# SparkFun_Qwiic_Mux_Shield_with_JST.net
KiCad netlist of a schematic drawn in EAGLE
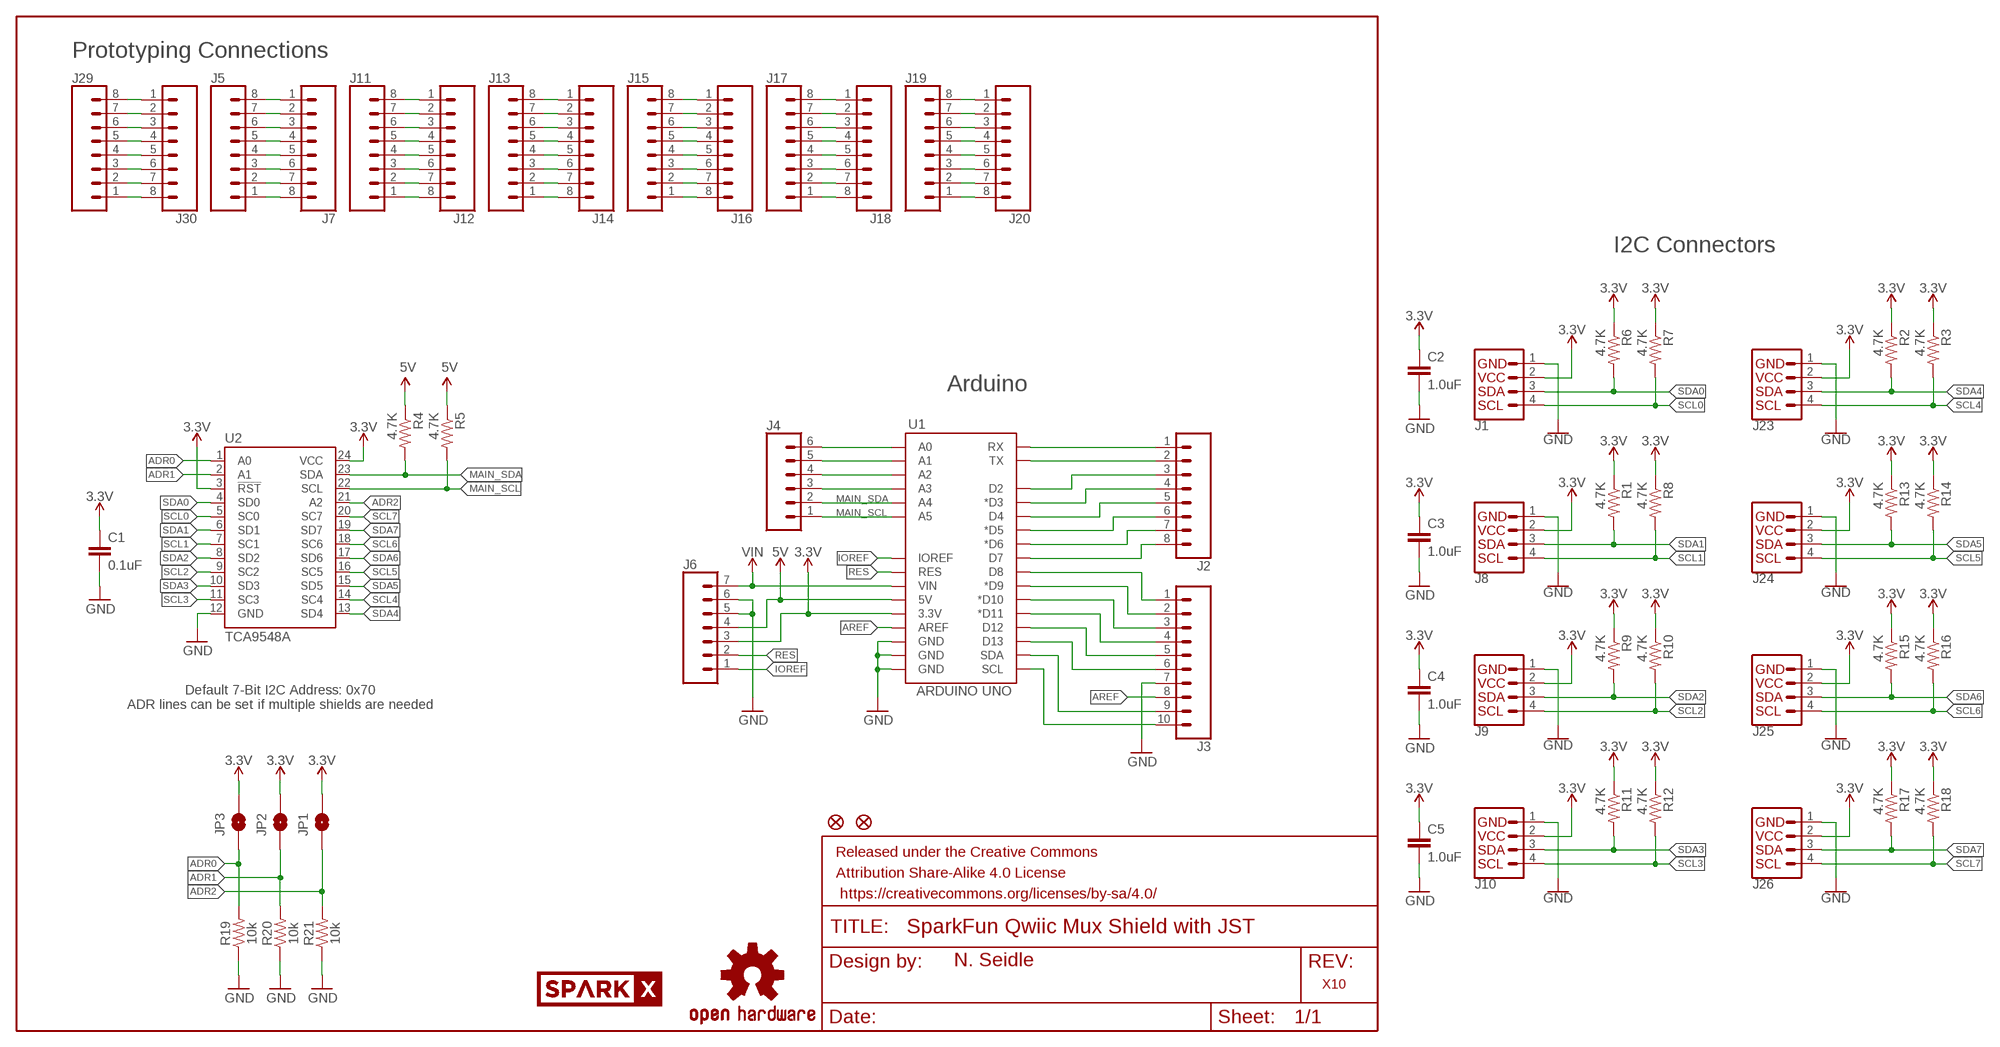
[diagram p0: schematic, sheet 1]

(export (version "E")
  (design (tool "Eeschema 10.0.6"))
  (components
    (comp (ref "C1")
      (value "0.1uF")
      (footprint "eagle-import:0603")
      (libsource (lib "eagle-import") (part "0.1UF-0603-25V-(+80/-20%)"))
    )
    (comp (ref "C2")
      (value "1.0uF")
      (footprint "eagle-import:0603")
      (libsource (lib "eagle-import") (part "1.0UF-0603-16V-10%"))
    )
    (comp (ref "C3")
      (value "1.0uF")
      (footprint "eagle-import:0603")
      (libsource (lib "eagle-import") (part "1.0UF-0603-16V-10%"))
    )
    (comp (ref "C4")
      (value "1.0uF")
      (footprint "eagle-import:0603")
      (libsource (lib "eagle-import") (part "1.0UF-0603-16V-10%"))
    )
    (comp (ref "C5")
      (value "1.0uF")
      (footprint "eagle-import:0603")
      (libsource (lib "eagle-import") (part "1.0UF-0603-16V-10%"))
    )
    (comp (ref "FD1")
      (value "FIDUCIAL1X2")
      (footprint "eagle-import:FIDUCIAL-1X2")
      (libsource (lib "eagle-import") (part "FIDUCIAL1X2"))
    )
    (comp (ref "FD2")
      (value "FIDUCIAL1X2")
      (footprint "eagle-import:FIDUCIAL-1X2")
      (libsource (lib "eagle-import") (part "FIDUCIAL1X2"))
    )
    (comp (ref "FRAME1")
      (value "FRAME-LETTER")
      (footprint "eagle-import:CREATIVE_COMMONS")
      (libsource (lib "eagle-import") (part "FRAME-LETTER"))
    )
    (comp (ref "J1")
      (value "I2C_STANDARDJS-1MM")
      (footprint "eagle-import:1X04_1MM_RA")
      (libsource (lib "eagle-import") (part "I2C_STANDARDJS-1MM"))
    )
    (comp (ref "J2")
      (value "CONN_08NO_SILK_FEMALE_PTH")
      (footprint "eagle-import:1X08_NO_SILK")
      (libsource (lib "eagle-import") (part "CONN_08NO_SILK_FEMALE_PTH"))
    )
    (comp (ref "J3")
      (value "CONN_10NO_SILK_PTH_FEMALE")
      (footprint "eagle-import:1X10_NO_SILK")
      (libsource (lib "eagle-import") (part "CONN_10NO_SILK_PTH_FEMALE"))
    )
    (comp (ref "J4")
      (value "CONN_06NO_SILK_FEMALE_PTH")
      (footprint "eagle-import:1X06_NO_SILK")
      (libsource (lib "eagle-import") (part "CONN_06NO_SILK_FEMALE_PTH"))
    )
    (comp (ref "J5")
      (value "CONN_08NO_SILK_FEMALE_PTH")
      (footprint "eagle-import:1X08_NO_SILK")
      (libsource (lib "eagle-import") (part "CONN_08NO_SILK_FEMALE_PTH"))
    )
    (comp (ref "J6")
      (value "CONN_07NO_SILK")
      (footprint "eagle-import:1X07_NO_SILK")
      (libsource (lib "eagle-import") (part "CONN_07NO_SILK"))
    )
    (comp (ref "J7")
      (value "CONN_08NO_SILK_FEMALE_PTH")
      (footprint "eagle-import:1X08_NO_SILK")
      (libsource (lib "eagle-import") (part "CONN_08NO_SILK_FEMALE_PTH"))
    )
    (comp (ref "J8")
      (value "I2C_STANDARDJS-1MM")
      (footprint "eagle-import:1X04_1MM_RA")
      (libsource (lib "eagle-import") (part "I2C_STANDARDJS-1MM"))
    )
    (comp (ref "J9")
      (value "I2C_STANDARDJS-1MM")
      (footprint "eagle-import:1X04_1MM_RA")
      (libsource (lib "eagle-import") (part "I2C_STANDARDJS-1MM"))
    )
    (comp (ref "J10")
      (value "I2C_STANDARDJS-1MM")
      (footprint "eagle-import:1X04_1MM_RA")
      (libsource (lib "eagle-import") (part "I2C_STANDARDJS-1MM"))
    )
    (comp (ref "J11")
      (value "CONN_08NO_SILK_FEMALE_PTH")
      (footprint "eagle-import:1X08_NO_SILK")
      (libsource (lib "eagle-import") (part "CONN_08NO_SILK_FEMALE_PTH"))
    )
    (comp (ref "J12")
      (value "CONN_08NO_SILK_FEMALE_PTH")
      (footprint "eagle-import:1X08_NO_SILK")
      (libsource (lib "eagle-import") (part "CONN_08NO_SILK_FEMALE_PTH"))
    )
    (comp (ref "J13")
      (value "CONN_08NO_SILK_FEMALE_PTH")
      (footprint "eagle-import:1X08_NO_SILK")
      (libsource (lib "eagle-import") (part "CONN_08NO_SILK_FEMALE_PTH"))
    )
    (comp (ref "J14")
      (value "CONN_08NO_SILK_FEMALE_PTH")
      (footprint "eagle-import:1X08_NO_SILK")
      (libsource (lib "eagle-import") (part "CONN_08NO_SILK_FEMALE_PTH"))
    )
    (comp (ref "J15")
      (value "CONN_08NO_SILK_FEMALE_PTH")
      (footprint "eagle-import:1X08_NO_SILK")
      (libsource (lib "eagle-import") (part "CONN_08NO_SILK_FEMALE_PTH"))
    )
    (comp (ref "J16")
      (value "CONN_08NO_SILK_FEMALE_PTH")
      (footprint "eagle-import:1X08_NO_SILK")
      (libsource (lib "eagle-import") (part "CONN_08NO_SILK_FEMALE_PTH"))
    )
    (comp (ref "J17")
      (value "CONN_08NO_SILK_FEMALE_PTH")
      (footprint "eagle-import:1X08_NO_SILK")
      (libsource (lib "eagle-import") (part "CONN_08NO_SILK_FEMALE_PTH"))
    )
    (comp (ref "J18")
      (value "CONN_08NO_SILK_FEMALE_PTH")
      (footprint "eagle-import:1X08_NO_SILK")
      (libsource (lib "eagle-import") (part "CONN_08NO_SILK_FEMALE_PTH"))
    )
    (comp (ref "J19")
      (value "CONN_08NO_SILK_FEMALE_PTH")
      (footprint "eagle-import:1X08_NO_SILK")
      (libsource (lib "eagle-import") (part "CONN_08NO_SILK_FEMALE_PTH"))
    )
    (comp (ref "J20")
      (value "CONN_08NO_SILK_FEMALE_PTH")
      (footprint "eagle-import:1X08_NO_SILK")
      (libsource (lib "eagle-import") (part "CONN_08NO_SILK_FEMALE_PTH"))
    )
    (comp (ref "J23")
      (value "I2C_STANDARDSILK")
      (footprint "eagle-import:1X04")
      (libsource (lib "eagle-import") (part "I2C_STANDARDSILK"))
    )
    (comp (ref "J24")
      (value "I2C_STANDARDSILK")
      (footprint "eagle-import:1X04")
      (libsource (lib "eagle-import") (part "I2C_STANDARDSILK"))
    )
    (comp (ref "J25")
      (value "I2C_STANDARDSILK")
      (footprint "eagle-import:1X04")
      (libsource (lib "eagle-import") (part "I2C_STANDARDSILK"))
    )
    (comp (ref "J26")
      (value "I2C_STANDARDSILK")
      (footprint "eagle-import:1X04")
      (libsource (lib "eagle-import") (part "I2C_STANDARDSILK"))
    )
    (comp (ref "J29")
      (value "CONN_08NO_SILK_FEMALE_PTH")
      (footprint "eagle-import:1X08_NO_SILK")
      (libsource (lib "eagle-import") (part "CONN_08NO_SILK_FEMALE_PTH"))
    )
    (comp (ref "J30")
      (value "CONN_08NO_SILK_FEMALE_PTH")
      (footprint "eagle-import:1X08_NO_SILK")
      (libsource (lib "eagle-import") (part "CONN_08NO_SILK_FEMALE_PTH"))
    )
    (comp (ref "JP1")
      (value "JUMPER-SMT_2_NO_SILK")
      (footprint "eagle-import:SMT-JUMPER_2_NO_SILK")
      (libsource (lib "eagle-import") (part "JUMPER-SMT_2_NO_SILK"))
    )
    (comp (ref "JP2")
      (value "JUMPER-SMT_2_NO_SILK")
      (footprint "eagle-import:SMT-JUMPER_2_NO_SILK")
      (libsource (lib "eagle-import") (part "JUMPER-SMT_2_NO_SILK"))
    )
    (comp (ref "JP3")
      (value "JUMPER-SMT_2_NO_SILK")
      (footprint "eagle-import:SMT-JUMPER_2_NO_SILK")
      (libsource (lib "eagle-import") (part "JUMPER-SMT_2_NO_SILK"))
    )
    (comp (ref "LOGO1")
      (value "OSHW-LOGOMINI")
      (footprint "eagle-import:OSHW-LOGO-MINI")
      (libsource (lib "eagle-import") (part "OSHW-LOGOMINI"))
    )
    (comp (ref "R1")
      (value "4.7K")
      (footprint "eagle-import:0603-RES")
      (libsource (lib "eagle-import") (part "4.7KOHM-1/10W-1%(0603)"))
    )
    (comp (ref "R2")
      (value "4.7K")
      (footprint "eagle-import:0603-RES")
      (libsource (lib "eagle-import") (part "4.7KOHM-1/10W-1%(0603)"))
    )
    (comp (ref "R3")
      (value "4.7K")
      (footprint "eagle-import:0603-RES")
      (libsource (lib "eagle-import") (part "4.7KOHM-1/10W-1%(0603)"))
    )
    (comp (ref "R4")
      (value "4.7K")
      (footprint "eagle-import:0603-RES")
      (libsource (lib "eagle-import") (part "4.7KOHM-1/10W-1%(0603)"))
    )
    (comp (ref "R5")
      (value "4.7K")
      (footprint "eagle-import:0603-RES")
      (libsource (lib "eagle-import") (part "4.7KOHM-1/10W-1%(0603)"))
    )
    (comp (ref "R6")
      (value "4.7K")
      (footprint "eagle-import:0603-RES")
      (libsource (lib "eagle-import") (part "4.7KOHM-1/10W-1%(0603)"))
    )
    (comp (ref "R7")
      (value "4.7K")
      (footprint "eagle-import:0603-RES")
      (libsource (lib "eagle-import") (part "4.7KOHM-1/10W-1%(0603)"))
    )
    (comp (ref "R8")
      (value "4.7K")
      (footprint "eagle-import:0603-RES")
      (libsource (lib "eagle-import") (part "4.7KOHM-1/10W-1%(0603)"))
    )
    (comp (ref "R9")
      (value "4.7K")
      (footprint "eagle-import:0603-RES")
      (libsource (lib "eagle-import") (part "4.7KOHM-1/10W-1%(0603)"))
    )
    (comp (ref "R10")
      (value "4.7K")
      (footprint "eagle-import:0603-RES")
      (libsource (lib "eagle-import") (part "4.7KOHM-1/10W-1%(0603)"))
    )
    (comp (ref "R11")
      (value "4.7K")
      (footprint "eagle-import:0603-RES")
      (libsource (lib "eagle-import") (part "4.7KOHM-1/10W-1%(0603)"))
    )
    (comp (ref "R12")
      (value "4.7K")
      (footprint "eagle-import:0603-RES")
      (libsource (lib "eagle-import") (part "4.7KOHM-1/10W-1%(0603)"))
    )
    (comp (ref "R13")
      (value "4.7K")
      (footprint "eagle-import:0603-RES")
      (libsource (lib "eagle-import") (part "4.7KOHM-1/10W-1%(0603)"))
    )
    (comp (ref "R14")
      (value "4.7K")
      (footprint "eagle-import:0603-RES")
      (libsource (lib "eagle-import") (part "4.7KOHM-1/10W-1%(0603)"))
    )
    (comp (ref "R15")
      (value "4.7K")
      (footprint "eagle-import:0603-RES")
      (libsource (lib "eagle-import") (part "4.7KOHM-1/10W-1%(0603)"))
    )
    (comp (ref "R16")
      (value "4.7K")
      (footprint "eagle-import:0603-RES")
      (libsource (lib "eagle-import") (part "4.7KOHM-1/10W-1%(0603)"))
    )
    (comp (ref "R17")
      (value "4.7K")
      (footprint "eagle-import:0603-RES")
      (libsource (lib "eagle-import") (part "4.7KOHM-1/10W-1%(0603)"))
    )
    (comp (ref "R18")
      (value "4.7K")
      (footprint "eagle-import:0603-RES")
      (libsource (lib "eagle-import") (part "4.7KOHM-1/10W-1%(0603)"))
    )
    (comp (ref "R19")
      (value "10k")
      (footprint "eagle-import:0603")
      (libsource (lib "eagle-import") (part "10KOHM-0603-1/10W-1%"))
    )
    (comp (ref "R20")
      (value "10k")
      (footprint "eagle-import:0603")
      (libsource (lib "eagle-import") (part "10KOHM-0603-1/10W-1%"))
    )
    (comp (ref "R21")
      (value "10k")
      (footprint "eagle-import:0603")
      (libsource (lib "eagle-import") (part "10KOHM-0603-1/10W-1%"))
    )
    (comp (ref "U$1")
      (value "SPARKX-LOGO3")
      (footprint "eagle-import:SPARKX-SMALL")
      (libsource (lib "eagle-import") (part "SPARKX-LOGO3"))
    )
    (comp (ref "U$2")
      (value "SPARKX-LOGO5")
      (footprint "eagle-import:SPARKX-LARGE")
      (libsource (lib "eagle-import") (part "SPARKX-LOGO5"))
    )
    (comp (ref "U1")
      (value "ARDUINO UNO")
      (footprint "eagle-import:UNO_R3_SHIELD_NOLABELS")
      (libsource (lib "eagle-import") (part "ARDUINO_R3_SHIELDNOLABELS"))
    )
    (comp (ref "U2")
      (value "TCA9548A")
      (footprint "eagle-import:TSSOP28")
      (libsource (lib "eagle-import") (part "TCA9548A"))
    )
  )
  (nets
    (net (code "1") (name "3.3V") (class "Default")
      (node (ref "C1") (pin "1") (pinfunction "1_1") (pintype "passive"))
      (node (ref "C2") (pin "1") (pinfunction "1_1") (pintype "passive"))
      (node (ref "C3") (pin "1") (pinfunction "1_1") (pintype "passive"))
      (node (ref "C4") (pin "1") (pinfunction "1_1") (pintype "passive"))
      (node (ref "C5") (pin "1") (pinfunction "1_1") (pintype "passive"))
      (node (ref "J1") (pin "2") (pinfunction "VCC_2") (pintype "power_in"))
      (node (ref "J10") (pin "2") (pinfunction "VCC_2") (pintype "power_in"))
      (node (ref "J23") (pin "2") (pinfunction "VCC_2") (pintype "power_in"))
      (node (ref "J24") (pin "2") (pinfunction "VCC_2") (pintype "power_in"))
      (node (ref "J25") (pin "2") (pinfunction "VCC_2") (pintype "power_in"))
      (node (ref "J26") (pin "2") (pinfunction "VCC_2") (pintype "power_in"))
      (node (ref "J6") (pin "3") (pinfunction "3_3") (pintype "passive"))
      (node (ref "J8") (pin "2") (pinfunction "VCC_2") (pintype "power_in"))
      (node (ref "J9") (pin "2") (pinfunction "VCC_2") (pintype "power_in"))
      (node (ref "JP1") (pin "2") (pinfunction "2_2") (pintype "passive"))
      (node (ref "JP2") (pin "2") (pinfunction "2_2") (pintype "passive"))
      (node (ref "JP3") (pin "2") (pinfunction "2_2") (pintype "passive"))
      (node (ref "R1") (pin "1") (pinfunction "1_1") (pintype "passive"))
      (node (ref "R10") (pin "1") (pinfunction "1_1") (pintype "passive"))
      (node (ref "R11") (pin "1") (pinfunction "1_1") (pintype "passive"))
      (node (ref "R12") (pin "1") (pinfunction "1_1") (pintype "passive"))
      (node (ref "R13") (pin "1") (pinfunction "1_1") (pintype "passive"))
      (node (ref "R14") (pin "1") (pinfunction "1_1") (pintype "passive"))
      (node (ref "R15") (pin "1") (pinfunction "1_1") (pintype "passive"))
      (node (ref "R16") (pin "1") (pinfunction "1_1") (pintype "passive"))
      (node (ref "R17") (pin "1") (pinfunction "1_1") (pintype "passive"))
      (node (ref "R18") (pin "1") (pinfunction "1_1") (pintype "passive"))
      (node (ref "R2") (pin "1") (pinfunction "1_1") (pintype "passive"))
      (node (ref "R3") (pin "1") (pinfunction "1_1") (pintype "passive"))
      (node (ref "R6") (pin "1") (pinfunction "1_1") (pintype "passive"))
      (node (ref "R7") (pin "1") (pinfunction "1_1") (pintype "passive"))
      (node (ref "R8") (pin "1") (pinfunction "1_1") (pintype "passive"))
      (node (ref "R9") (pin "1") (pinfunction "1_1") (pintype "passive"))
      (node (ref "U1") (pin "3.3V") (pinfunction "3.3V_3.3V") (pintype "bidirectional"))
      (node (ref "U2") (pin "24") (pinfunction "VCC_24") (pintype "bidirectional"))
      (node (ref "U2") (pin "3") (pinfunction "~{RST}_3") (pintype "bidirectional"))
    )
    (net (code "2") (name "5V") (class "Default")
      (node (ref "J6") (pin "4") (pinfunction "4_4") (pintype "passive"))
      (node (ref "R4") (pin "1") (pinfunction "1_1") (pintype "passive"))
      (node (ref "R5") (pin "1") (pinfunction "1_1") (pintype "passive"))
      (node (ref "U1") (pin "5V") (pinfunction "5V_5V") (pintype "bidirectional"))
    )
    (net (code "3") (name "ADR0") (class "Default")
      (node (ref "JP3") (pin "1") (pinfunction "1_1") (pintype "passive"))
      (node (ref "R19") (pin "2") (pinfunction "2_2") (pintype "passive"))
      (node (ref "U2") (pin "1") (pinfunction "A0_1") (pintype "bidirectional"))
    )
    (net (code "4") (name "ADR1") (class "Default")
      (node (ref "JP2") (pin "1") (pinfunction "1_1") (pintype "passive"))
      (node (ref "R20") (pin "2") (pinfunction "2_2") (pintype "passive"))
      (node (ref "U2") (pin "2") (pinfunction "A1_2") (pintype "bidirectional"))
    )
    (net (code "5") (name "ADR2") (class "Default")
      (node (ref "JP1") (pin "1") (pinfunction "1_1") (pintype "passive"))
      (node (ref "R21") (pin "2") (pinfunction "2_2") (pintype "passive"))
      (node (ref "U2") (pin "21") (pinfunction "A2_21") (pintype "bidirectional"))
    )
    (net (code "6") (name "AREF") (class "Default")
      (node (ref "J3") (pin "8") (pinfunction "8_8") (pintype "passive"))
      (node (ref "U1") (pin "AREF") (pinfunction "AREF_AREF") (pintype "bidirectional"))
    )
    (net (code "7") (name "GND") (class "Default")
      (node (ref "C1") (pin "2") (pinfunction "2_2") (pintype "passive"))
      (node (ref "C2") (pin "2") (pinfunction "2_2") (pintype "passive"))
      (node (ref "C3") (pin "2") (pinfunction "2_2") (pintype "passive"))
      (node (ref "C4") (pin "2") (pinfunction "2_2") (pintype "passive"))
      (node (ref "C5") (pin "2") (pinfunction "2_2") (pintype "passive"))
      (node (ref "J1") (pin "1") (pinfunction "GND_1") (pintype "power_in"))
      (node (ref "J10") (pin "1") (pinfunction "GND_1") (pintype "power_in"))
      (node (ref "J23") (pin "1") (pinfunction "GND_1") (pintype "power_in"))
      (node (ref "J24") (pin "1") (pinfunction "GND_1") (pintype "power_in"))
      (node (ref "J25") (pin "1") (pinfunction "GND_1") (pintype "power_in"))
      (node (ref "J26") (pin "1") (pinfunction "GND_1") (pintype "power_in"))
      (node (ref "J3") (pin "7") (pinfunction "7_7") (pintype "passive"))
      (node (ref "J6") (pin "5") (pinfunction "5_5") (pintype "passive"))
      (node (ref "J6") (pin "6") (pinfunction "6_6") (pintype "passive"))
      (node (ref "J8") (pin "1") (pinfunction "GND_1") (pintype "power_in"))
      (node (ref "J9") (pin "1") (pinfunction "GND_1") (pintype "power_in"))
      (node (ref "R19") (pin "1") (pinfunction "1_1") (pintype "passive"))
      (node (ref "R20") (pin "1") (pinfunction "1_1") (pintype "passive"))
      (node (ref "R21") (pin "1") (pinfunction "1_1") (pintype "passive"))
      (node (ref "U1") (pin "GND@0") (pinfunction "GND_GND@0") (pintype "bidirectional"))
      (node (ref "U1") (pin "GND@1") (pinfunction "GND_GND@1") (pintype "bidirectional"))
      (node (ref "U1") (pin "GND@2") (pinfunction "GND_GND@2") (pintype "bidirectional"))
      (node (ref "U2") (pin "12") (pinfunction "GND_12") (pintype "bidirectional"))
    )
    (net (code "8") (name "IOREF") (class "Default")
      (node (ref "J6") (pin "1") (pinfunction "1_1") (pintype "passive"))
      (node (ref "U1") (pin "IOREF") (pinfunction "IOREF_IOREF") (pintype "bidirectional"))
    )
    (net (code "9") (name "MAIN_SCL") (class "Default")
      (node (ref "J4") (pin "1") (pinfunction "1_1") (pintype "passive"))
      (node (ref "R5") (pin "2") (pinfunction "2_2") (pintype "passive"))
      (node (ref "U1") (pin "A5") (pinfunction "A5_A5") (pintype "bidirectional"))
      (node (ref "U2") (pin "22") (pinfunction "SCL_22") (pintype "bidirectional"))
    )
    (net (code "10") (name "MAIN_SDA") (class "Default")
      (node (ref "J4") (pin "2") (pinfunction "2_2") (pintype "passive"))
      (node (ref "R4") (pin "2") (pinfunction "2_2") (pintype "passive"))
      (node (ref "U1") (pin "A4") (pinfunction "A4_A4") (pintype "bidirectional"))
      (node (ref "U2") (pin "23") (pinfunction "SDA_23") (pintype "bidirectional"))
    )
    (net (code "11") (name "Net-(J2-Pad1)") (class "Default")
      (node (ref "J2") (pin "1") (pinfunction "1_1") (pintype "passive"))
      (node (ref "U1") (pin "RX") (pinfunction "RX_RX") (pintype "bidirectional"))
    )
    (net (code "12") (name "Net-(J2-Pad2)") (class "Default")
      (node (ref "J2") (pin "2") (pinfunction "2_2") (pintype "passive"))
      (node (ref "U1") (pin "TX") (pinfunction "TX_TX") (pintype "bidirectional"))
    )
    (net (code "13") (name "Net-(J2-Pad3)") (class "Default")
      (node (ref "J2") (pin "3") (pinfunction "3_3") (pintype "passive"))
      (node (ref "U1") (pin "D2") (pinfunction "D2_D2") (pintype "bidirectional"))
    )
    (net (code "14") (name "Net-(J2-Pad5)") (class "Default")
      (node (ref "J2") (pin "5") (pinfunction "5_5") (pintype "passive"))
      (node (ref "U1") (pin "D4") (pinfunction "D4_D4") (pintype "bidirectional"))
    )
    (net (code "15") (name "Net-(J2-Pad8)") (class "Default")
      (node (ref "J2") (pin "8") (pinfunction "8_8") (pintype "passive"))
      (node (ref "U1") (pin "D7") (pinfunction "D7_D7") (pintype "bidirectional"))
    )
    (net (code "16") (name "Net-(J3-Pad1)") (class "Default")
      (node (ref "J3") (pin "1") (pinfunction "1_1") (pintype "passive"))
      (node (ref "U1") (pin "D8") (pinfunction "D8_D8") (pintype "bidirectional"))
    )
    (net (code "17") (name "Net-(J3-Pad5)") (class "Default")
      (node (ref "J3") (pin "5") (pinfunction "5_5") (pintype "passive"))
      (node (ref "U1") (pin "D12") (pinfunction "D12_D12") (pintype "bidirectional"))
    )
    (net (code "18") (name "Net-(J3-Pad6)") (class "Default")
      (node (ref "J3") (pin "6") (pinfunction "6_6") (pintype "passive"))
      (node (ref "U1") (pin "D13") (pinfunction "D13_D13") (pintype "bidirectional"))
    )
    (net (code "19") (name "Net-(J3-Pad9)") (class "Default")
      (node (ref "J3") (pin "9") (pinfunction "9_9") (pintype "passive"))
      (node (ref "U1") (pin "SDA") (pinfunction "SDA_SDA") (pintype "bidirectional"))
    )
    (net (code "20") (name "Net-(J3-Pad10)") (class "Default")
      (node (ref "J3") (pin "10") (pinfunction "10_10") (pintype "passive"))
      (node (ref "U1") (pin "SCL") (pinfunction "SCL_SCL") (pintype "bidirectional"))
    )
    (net (code "21") (name "Net-(J4-Pad3)") (class "Default")
      (node (ref "J4") (pin "3") (pinfunction "3_3") (pintype "passive"))
      (node (ref "U1") (pin "A3") (pinfunction "A3_A3") (pintype "bidirectional"))
    )
    (net (code "22") (name "Net-(J4-Pad4)") (class "Default")
      (node (ref "J4") (pin "4") (pinfunction "4_4") (pintype "passive"))
      (node (ref "U1") (pin "A2") (pinfunction "A2_A2") (pintype "bidirectional"))
    )
    (net (code "23") (name "Net-(J4-Pad5)") (class "Default")
      (node (ref "J4") (pin "5") (pinfunction "5_5") (pintype "passive"))
      (node (ref "U1") (pin "A1") (pinfunction "A1_A1") (pintype "bidirectional"))
    )
    (net (code "24") (name "Net-(J4-Pad6)") (class "Default")
      (node (ref "J4") (pin "6") (pinfunction "6_6") (pintype "passive"))
      (node (ref "U1") (pin "A0") (pinfunction "A0_A0") (pintype "bidirectional"))
    )
    (net (code "25") (name "Net-(J5-Pad1)") (class "Default")
      (node (ref "J5") (pin "1") (pinfunction "1_1") (pintype "passive"))
      (node (ref "J7") (pin "8") (pinfunction "8_8") (pintype "passive"))
    )
    (net (code "26") (name "Net-(J5-Pad2)") (class "Default")
      (node (ref "J5") (pin "2") (pinfunction "2_2") (pintype "passive"))
      (node (ref "J7") (pin "7") (pinfunction "7_7") (pintype "passive"))
    )
    (net (code "27") (name "Net-(J5-Pad3)") (class "Default")
      (node (ref "J5") (pin "3") (pinfunction "3_3") (pintype "passive"))
      (node (ref "J7") (pin "6") (pinfunction "6_6") (pintype "passive"))
    )
    (net (code "28") (name "Net-(J5-Pad4)") (class "Default")
      (node (ref "J5") (pin "4") (pinfunction "4_4") (pintype "passive"))
      (node (ref "J7") (pin "5") (pinfunction "5_5") (pintype "passive"))
    )
    (net (code "29") (name "Net-(J5-Pad5)") (class "Default")
      (node (ref "J5") (pin "5") (pinfunction "5_5") (pintype "passive"))
      (node (ref "J7") (pin "4") (pinfunction "4_4") (pintype "passive"))
    )
    (net (code "30") (name "Net-(J5-Pad6)") (class "Default")
      (node (ref "J5") (pin "6") (pinfunction "6_6") (pintype "passive"))
      (node (ref "J7") (pin "3") (pinfunction "3_3") (pintype "passive"))
    )
    (net (code "31") (name "Net-(J5-Pad7)") (class "Default")
      (node (ref "J5") (pin "7") (pinfunction "7_7") (pintype "passive"))
      (node (ref "J7") (pin "2") (pinfunction "2_2") (pintype "passive"))
    )
    (net (code "32") (name "Net-(J5-Pad8)") (class "Default")
      (node (ref "J5") (pin "8") (pinfunction "8_8") (pintype "passive"))
      (node (ref "J7") (pin "1") (pinfunction "1_1") (pintype "passive"))
    )
    (net (code "33") (name "Net-(J11-Pad1)") (class "Default")
      (node (ref "J11") (pin "1") (pinfunction "1_1") (pintype "passive"))
      (node (ref "J12") (pin "8") (pinfunction "8_8") (pintype "passive"))
    )
    (net (code "34") (name "Net-(J11-Pad2)") (class "Default")
      (node (ref "J11") (pin "2") (pinfunction "2_2") (pintype "passive"))
      (node (ref "J12") (pin "7") (pinfunction "7_7") (pintype "passive"))
    )
    (net (code "35") (name "Net-(J11-Pad3)") (class "Default")
      (node (ref "J11") (pin "3") (pinfunction "3_3") (pintype "passive"))
      (node (ref "J12") (pin "6") (pinfunction "6_6") (pintype "passive"))
    )
    (net (code "36") (name "Net-(J11-Pad4)") (class "Default")
      (node (ref "J11") (pin "4") (pinfunction "4_4") (pintype "passive"))
      (node (ref "J12") (pin "5") (pinfunction "5_5") (pintype "passive"))
    )
    (net (code "37") (name "Net-(J11-Pad5)") (class "Default")
      (node (ref "J11") (pin "5") (pinfunction "5_5") (pintype "passive"))
      (node (ref "J12") (pin "4") (pinfunction "4_4") (pintype "passive"))
    )
    (net (code "38") (name "Net-(J11-Pad6)") (class "Default")
      (node (ref "J11") (pin "6") (pinfunction "6_6") (pintype "passive"))
      (node (ref "J12") (pin "3") (pinfunction "3_3") (pintype "passive"))
    )
    (net (code "39") (name "Net-(J11-Pad7)") (class "Default")
      (node (ref "J11") (pin "7") (pinfunction "7_7") (pintype "passive"))
      (node (ref "J12") (pin "2") (pinfunction "2_2") (pintype "passive"))
    )
    (net (code "40") (name "Net-(J11-Pad8)") (class "Default")
      (node (ref "J11") (pin "8") (pinfunction "8_8") (pintype "passive"))
      (node (ref "J12") (pin "1") (pinfunction "1_1") (pintype "passive"))
    )
    (net (code "41") (name "Net-(J13-Pad1)") (class "Default")
      (node (ref "J13") (pin "1") (pinfunction "1_1") (pintype "passive"))
      (node (ref "J14") (pin "8") (pinfunction "8_8") (pintype "passive"))
    )
    (net (code "42") (name "Net-(J13-Pad2)") (class "Default")
      (node (ref "J13") (pin "2") (pinfunction "2_2") (pintype "passive"))
      (node (ref "J14") (pin "7") (pinfunction "7_7") (pintype "passive"))
    )
    (net (code "43") (name "Net-(J13-Pad3)") (class "Default")
      (node (ref "J13") (pin "3") (pinfunction "3_3") (pintype "passive"))
      (node (ref "J14") (pin "6") (pinfunction "6_6") (pintype "passive"))
    )
    (net (code "44") (name "Net-(J13-Pad4)") (class "Default")
      (node (ref "J13") (pin "4") (pinfunction "4_4") (pintype "passive"))
      (node (ref "J14") (pin "5") (pinfunction "5_5") (pintype "passive"))
    )
    (net (code "45") (name "Net-(J13-Pad5)") (class "Default")
      (node (ref "J13") (pin "5") (pinfunction "5_5") (pintype "passive"))
      (node (ref "J14") (pin "4") (pinfunction "4_4") (pintype "passive"))
    )
    (net (code "46") (name "Net-(J13-Pad6)") (class "Default")
      (node (ref "J13") (pin "6") (pinfunction "6_6") (pintype "passive"))
      (node (ref "J14") (pin "3") (pinfunction "3_3") (pintype "passive"))
    )
    (net (code "47") (name "Net-(J13-Pad7)") (class "Default")
      (node (ref "J13") (pin "7") (pinfunction "7_7") (pintype "passive"))
      (node (ref "J14") (pin "2") (pinfunction "2_2") (pintype "passive"))
    )
    (net (code "48") (name "Net-(J13-Pad8)") (class "Default")
      (node (ref "J13") (pin "8") (pinfunction "8_8") (pintype "passive"))
      (node (ref "J14") (pin "1") (pinfunction "1_1") (pintype "passive"))
    )
    (net (code "49") (name "Net-(J15-Pad1)") (class "Default")
      (node (ref "J15") (pin "1") (pinfunction "1_1") (pintype "passive"))
      (node (ref "J16") (pin "8") (pinfunction "8_8") (pintype "passive"))
    )
    (net (code "50") (name "Net-(J15-Pad2)") (class "Default")
      (node (ref "J15") (pin "2") (pinfunction "2_2") (pintype "passive"))
      (node (ref "J16") (pin "7") (pinfunction "7_7") (pintype "passive"))
    )
    (net (code "51") (name "Net-(J15-Pad3)") (class "Default")
      (node (ref "J15") (pin "3") (pinfunction "3_3") (pintype "passive"))
      (node (ref "J16") (pin "6") (pinfunction "6_6") (pintype "passive"))
    )
    (net (code "52") (name "Net-(J15-Pad4)") (class "Default")
      (node (ref "J15") (pin "4") (pinfunction "4_4") (pintype "passive"))
      (node (ref "J16") (pin "5") (pinfunction "5_5") (pintype "passive"))
    )
    (net (code "53") (name "Net-(J15-Pad5)") (class "Default")
      (node (ref "J15") (pin "5") (pinfunction "5_5") (pintype "passive"))
      (node (ref "J16") (pin "4") (pinfunction "4_4") (pintype "passive"))
    )
    (net (code "54") (name "Net-(J15-Pad6)") (class "Default")
      (node (ref "J15") (pin "6") (pinfunction "6_6") (pintype "passive"))
      (node (ref "J16") (pin "3") (pinfunction "3_3") (pintype "passive"))
    )
    (net (code "55") (name "Net-(J15-Pad7)") (class "Default")
      (node (ref "J15") (pin "7") (pinfunction "7_7") (pintype "passive"))
      (node (ref "J16") (pin "2") (pinfunction "2_2") (pintype "passive"))
    )
    (net (code "56") (name "Net-(J15-Pad8)") (class "Default")
      (node (ref "J15") (pin "8") (pinfunction "8_8") (pintype "passive"))
      (node (ref "J16") (pin "1") (pinfunction "1_1") (pintype "passive"))
    )
    (net (code "57") (name "Net-(J17-Pad1)") (class "Default")
      (node (ref "J17") (pin "1") (pinfunction "1_1") (pintype "passive"))
      (node (ref "J18") (pin "8") (pinfunction "8_8") (pintype "passive"))
    )
    (net (code "58") (name "Net-(J17-Pad2)") (class "Default")
      (node (ref "J17") (pin "2") (pinfunction "2_2") (pintype "passive"))
      (node (ref "J18") (pin "7") (pinfunction "7_7") (pintype "passive"))
    )
    (net (code "59") (name "Net-(J17-Pad3)") (class "Default")
      (node (ref "J17") (pin "3") (pinfunction "3_3") (pintype "passive"))
      (node (ref "J18") (pin "6") (pinfunction "6_6") (pintype "passive"))
    )
    (net (code "60") (name "Net-(J17-Pad4)") (class "Default")
      (node (ref "J17") (pin "4") (pinfunction "4_4") (pintype "passive"))
      (node (ref "J18") (pin "5") (pinfunction "5_5") (pintype "passive"))
    )
    (net (code "61") (name "Net-(J17-Pad5)") (class "Default")
      (node (ref "J17") (pin "5") (pinfunction "5_5") (pintype "passive"))
      (node (ref "J18") (pin "4") (pinfunction "4_4") (pintype "passive"))
    )
    (net (code "62") (name "Net-(J17-Pad6)") (class "Default")
      (node (ref "J17") (pin "6") (pinfunction "6_6") (pintype "passive"))
      (node (ref "J18") (pin "3") (pinfunction "3_3") (pintype "passive"))
    )
    (net (code "63") (name "Net-(J17-Pad7)") (class "Default")
      (node (ref "J17") (pin "7") (pinfunction "7_7") (pintype "passive"))
      (node (ref "J18") (pin "2") (pinfunction "2_2") (pintype "passive"))
    )
    (net (code "64") (name "Net-(J17-Pad8)") (class "Default")
      (node (ref "J17") (pin "8") (pinfunction "8_8") (pintype "passive"))
      (node (ref "J18") (pin "1") (pinfunction "1_1") (pintype "passive"))
    )
    (net (code "65") (name "Net-(J19-Pad1)") (class "Default")
      (node (ref "J19") (pin "1") (pinfunction "1_1") (pintype "passive"))
      (node (ref "J20") (pin "8") (pinfunction "8_8") (pintype "passive"))
    )
    (net (code "66") (name "Net-(J19-Pad2)") (class "Default")
      (node (ref "J19") (pin "2") (pinfunction "2_2") (pintype "passive"))
      (node (ref "J20") (pin "7") (pinfunction "7_7") (pintype "passive"))
    )
    (net (code "67") (name "Net-(J19-Pad3)") (class "Default")
      (node (ref "J19") (pin "3") (pinfunction "3_3") (pintype "passive"))
      (node (ref "J20") (pin "6") (pinfunction "6_6") (pintype "passive"))
    )
    (net (code "68") (name "Net-(J19-Pad4)") (class "Default")
      (node (ref "J19") (pin "4") (pinfunction "4_4") (pintype "passive"))
      (node (ref "J20") (pin "5") (pinfunction "5_5") (pintype "passive"))
    )
    (net (code "69") (name "Net-(J19-Pad5)") (class "Default")
      (node (ref "J19") (pin "5") (pinfunction "5_5") (pintype "passive"))
      (node (ref "J20") (pin "4") (pinfunction "4_4") (pintype "passive"))
    )
    (net (code "70") (name "Net-(J19-Pad6)") (class "Default")
      (node (ref "J19") (pin "6") (pinfunction "6_6") (pintype "passive"))
      (node (ref "J20") (pin "3") (pinfunction "3_3") (pintype "passive"))
    )
    (net (code "71") (name "Net-(J19-Pad7)") (class "Default")
      (node (ref "J19") (pin "7") (pinfunction "7_7") (pintype "passive"))
      (node (ref "J20") (pin "2") (pinfunction "2_2") (pintype "passive"))
    )
    (net (code "72") (name "Net-(J19-Pad8)") (class "Default")
      (node (ref "J19") (pin "8") (pinfunction "8_8") (pintype "passive"))
      (node (ref "J20") (pin "1") (pinfunction "1_1") (pintype "passive"))
    )
    (net (code "73") (name "Net-(J29-Pad1)") (class "Default")
      (node (ref "J29") (pin "1") (pinfunction "1_1") (pintype "passive"))
      (node (ref "J30") (pin "8") (pinfunction "8_8") (pintype "passive"))
    )
    (net (code "74") (name "Net-(J29-Pad2)") (class "Default")
      (node (ref "J29") (pin "2") (pinfunction "2_2") (pintype "passive"))
      (node (ref "J30") (pin "7") (pinfunction "7_7") (pintype "passive"))
    )
    (net (code "75") (name "Net-(J29-Pad3)") (class "Default")
      (node (ref "J29") (pin "3") (pinfunction "3_3") (pintype "passive"))
      (node (ref "J30") (pin "6") (pinfunction "6_6") (pintype "passive"))
    )
    (net (code "76") (name "Net-(J29-Pad4)") (class "Default")
      (node (ref "J29") (pin "4") (pinfunction "4_4") (pintype "passive"))
      (node (ref "J30") (pin "5") (pinfunction "5_5") (pintype "passive"))
    )
    (net (code "77") (name "Net-(J29-Pad5)") (class "Default")
      (node (ref "J29") (pin "5") (pinfunction "5_5") (pintype "passive"))
      (node (ref "J30") (pin "4") (pinfunction "4_4") (pintype "passive"))
    )
    (net (code "78") (name "Net-(J29-Pad6)") (class "Default")
      (node (ref "J29") (pin "6") (pinfunction "6_6") (pintype "passive"))
      (node (ref "J30") (pin "3") (pinfunction "3_3") (pintype "passive"))
    )
    (net (code "79") (name "Net-(J29-Pad7)") (class "Default")
      (node (ref "J29") (pin "7") (pinfunction "7_7") (pintype "passive"))
      (node (ref "J30") (pin "2") (pinfunction "2_2") (pintype "passive"))
    )
    (net (code "80") (name "Net-(J29-Pad8)") (class "Default")
      (node (ref "J29") (pin "8") (pinfunction "8_8") (pintype "passive"))
      (node (ref "J30") (pin "1") (pinfunction "1_1") (pintype "passive"))
    )
    (net (code "81") (name "Net-(U1-*D3)") (class "Default")
      (node (ref "J2") (pin "4") (pinfunction "4_4") (pintype "passive"))
      (node (ref "U1") (pin "D3") (pinfunction "*D3_D3") (pintype "bidirectional"))
    )
    (net (code "82") (name "Net-(U1-*D5)") (class "Default")
      (node (ref "J2") (pin "6") (pinfunction "6_6") (pintype "passive"))
      (node (ref "U1") (pin "D5") (pinfunction "*D5_D5") (pintype "bidirectional"))
    )
    (net (code "83") (name "Net-(U1-*D6)") (class "Default")
      (node (ref "J2") (pin "7") (pinfunction "7_7") (pintype "passive"))
      (node (ref "U1") (pin "D6") (pinfunction "*D6_D6") (pintype "bidirectional"))
    )
    (net (code "84") (name "Net-(U1-*D9)") (class "Default")
      (node (ref "J3") (pin "2") (pinfunction "2_2") (pintype "passive"))
      (node (ref "U1") (pin "D9") (pinfunction "*D9_D9") (pintype "bidirectional"))
    )
    (net (code "85") (name "Net-(U1-*D10)") (class "Default")
      (node (ref "J3") (pin "3") (pinfunction "3_3") (pintype "passive"))
      (node (ref "U1") (pin "D10") (pinfunction "*D10_D10") (pintype "bidirectional"))
    )
    (net (code "86") (name "Net-(U1-*D11)") (class "Default")
      (node (ref "J3") (pin "4") (pinfunction "4_4") (pintype "passive"))
      (node (ref "U1") (pin "D11") (pinfunction "*D11_D11") (pintype "bidirectional"))
    )
    (net (code "87") (name "RES") (class "Default")
      (node (ref "J6") (pin "2") (pinfunction "2_2") (pintype "passive"))
      (node (ref "U1") (pin "RES") (pinfunction "RES_RES") (pintype "bidirectional"))
    )
    (net (code "88") (name "SCL0") (class "Default")
      (node (ref "J1") (pin "4") (pinfunction "SCL_4") (pintype "passive"))
      (node (ref "R7") (pin "2") (pinfunction "2_2") (pintype "passive"))
      (node (ref "U2") (pin "5") (pinfunction "SC0_5") (pintype "bidirectional"))
    )
    (net (code "89") (name "SCL1") (class "Default")
      (node (ref "J8") (pin "4") (pinfunction "SCL_4") (pintype "passive"))
      (node (ref "R8") (pin "2") (pinfunction "2_2") (pintype "passive"))
      (node (ref "U2") (pin "7") (pinfunction "SC1_7") (pintype "bidirectional"))
    )
    (net (code "90") (name "SCL2") (class "Default")
      (node (ref "J9") (pin "4") (pinfunction "SCL_4") (pintype "passive"))
      (node (ref "R10") (pin "2") (pinfunction "2_2") (pintype "passive"))
      (node (ref "U2") (pin "9") (pinfunction "SC2_9") (pintype "bidirectional"))
    )
    (net (code "91") (name "SCL3") (class "Default")
      (node (ref "J10") (pin "4") (pinfunction "SCL_4") (pintype "passive"))
      (node (ref "R12") (pin "2") (pinfunction "2_2") (pintype "passive"))
      (node (ref "U2") (pin "11") (pinfunction "SC3_11") (pintype "bidirectional"))
    )
    (net (code "92") (name "SCL4") (class "Default")
      (node (ref "J23") (pin "4") (pinfunction "SCL_4") (pintype "passive"))
      (node (ref "R3") (pin "2") (pinfunction "2_2") (pintype "passive"))
      (node (ref "U2") (pin "14") (pinfunction "SC4_14") (pintype "bidirectional"))
    )
    (net (code "93") (name "SCL5") (class "Default")
      (node (ref "J24") (pin "4") (pinfunction "SCL_4") (pintype "passive"))
      (node (ref "R14") (pin "2") (pinfunction "2_2") (pintype "passive"))
      (node (ref "U2") (pin "16") (pinfunction "SC5_16") (pintype "bidirectional"))
    )
    (net (code "94") (name "SCL6") (class "Default")
      (node (ref "J25") (pin "4") (pinfunction "SCL_4") (pintype "passive"))
      (node (ref "R16") (pin "2") (pinfunction "2_2") (pintype "passive"))
      (node (ref "U2") (pin "18") (pinfunction "SC6_18") (pintype "bidirectional"))
    )
    (net (code "95") (name "SCL7") (class "Default")
      (node (ref "J26") (pin "4") (pinfunction "SCL_4") (pintype "passive"))
      (node (ref "R18") (pin "2") (pinfunction "2_2") (pintype "passive"))
      (node (ref "U2") (pin "20") (pinfunction "SC7_20") (pintype "bidirectional"))
    )
    (net (code "96") (name "SDA0") (class "Default")
      (node (ref "J1") (pin "3") (pinfunction "SDA_3") (pintype "passive"))
      (node (ref "R6") (pin "2") (pinfunction "2_2") (pintype "passive"))
      (node (ref "U2") (pin "4") (pinfunction "SD0_4") (pintype "bidirectional"))
    )
    (net (code "97") (name "SDA1") (class "Default")
      (node (ref "J8") (pin "3") (pinfunction "SDA_3") (pintype "passive"))
      (node (ref "R1") (pin "2") (pinfunction "2_2") (pintype "passive"))
      (node (ref "U2") (pin "6") (pinfunction "SD1_6") (pintype "bidirectional"))
    )
    (net (code "98") (name "SDA2") (class "Default")
      (node (ref "J9") (pin "3") (pinfunction "SDA_3") (pintype "passive"))
      (node (ref "R9") (pin "2") (pinfunction "2_2") (pintype "passive"))
      (node (ref "U2") (pin "8") (pinfunction "SD2_8") (pintype "bidirectional"))
    )
    (net (code "99") (name "SDA3") (class "Default")
      (node (ref "J10") (pin "3") (pinfunction "SDA_3") (pintype "passive"))
      (node (ref "R11") (pin "2") (pinfunction "2_2") (pintype "passive"))
      (node (ref "U2") (pin "10") (pinfunction "SD3_10") (pintype "bidirectional"))
    )
    (net (code "100") (name "SDA4") (class "Default")
      (node (ref "J23") (pin "3") (pinfunction "SDA_3") (pintype "passive"))
      (node (ref "R2") (pin "2") (pinfunction "2_2") (pintype "passive"))
      (node (ref "U2") (pin "13") (pinfunction "SD4_13") (pintype "bidirectional"))
    )
    (net (code "101") (name "SDA5") (class "Default")
      (node (ref "J24") (pin "3") (pinfunction "SDA_3") (pintype "passive"))
      (node (ref "R13") (pin "2") (pinfunction "2_2") (pintype "passive"))
      (node (ref "U2") (pin "15") (pinfunction "SD5_15") (pintype "bidirectional"))
    )
    (net (code "102") (name "SDA6") (class "Default")
      (node (ref "J25") (pin "3") (pinfunction "SDA_3") (pintype "passive"))
      (node (ref "R15") (pin "2") (pinfunction "2_2") (pintype "passive"))
      (node (ref "U2") (pin "17") (pinfunction "SD6_17") (pintype "bidirectional"))
    )
    (net (code "103") (name "SDA7") (class "Default")
      (node (ref "J26") (pin "3") (pinfunction "SDA_3") (pintype "passive"))
      (node (ref "R17") (pin "2") (pinfunction "2_2") (pintype "passive"))
      (node (ref "U2") (pin "19") (pinfunction "SD7_19") (pintype "bidirectional"))
    )
    (net (code "104") (name "VIN") (class "Default")
      (node (ref "J6") (pin "7") (pinfunction "7_7") (pintype "passive"))
      (node (ref "U1") (pin "VIN") (pinfunction "VIN_VIN") (pintype "bidirectional"))
    )
  )
)
